# Custom_USB_N64.net
KiCad netlist of a schematic drawn in EAGLE
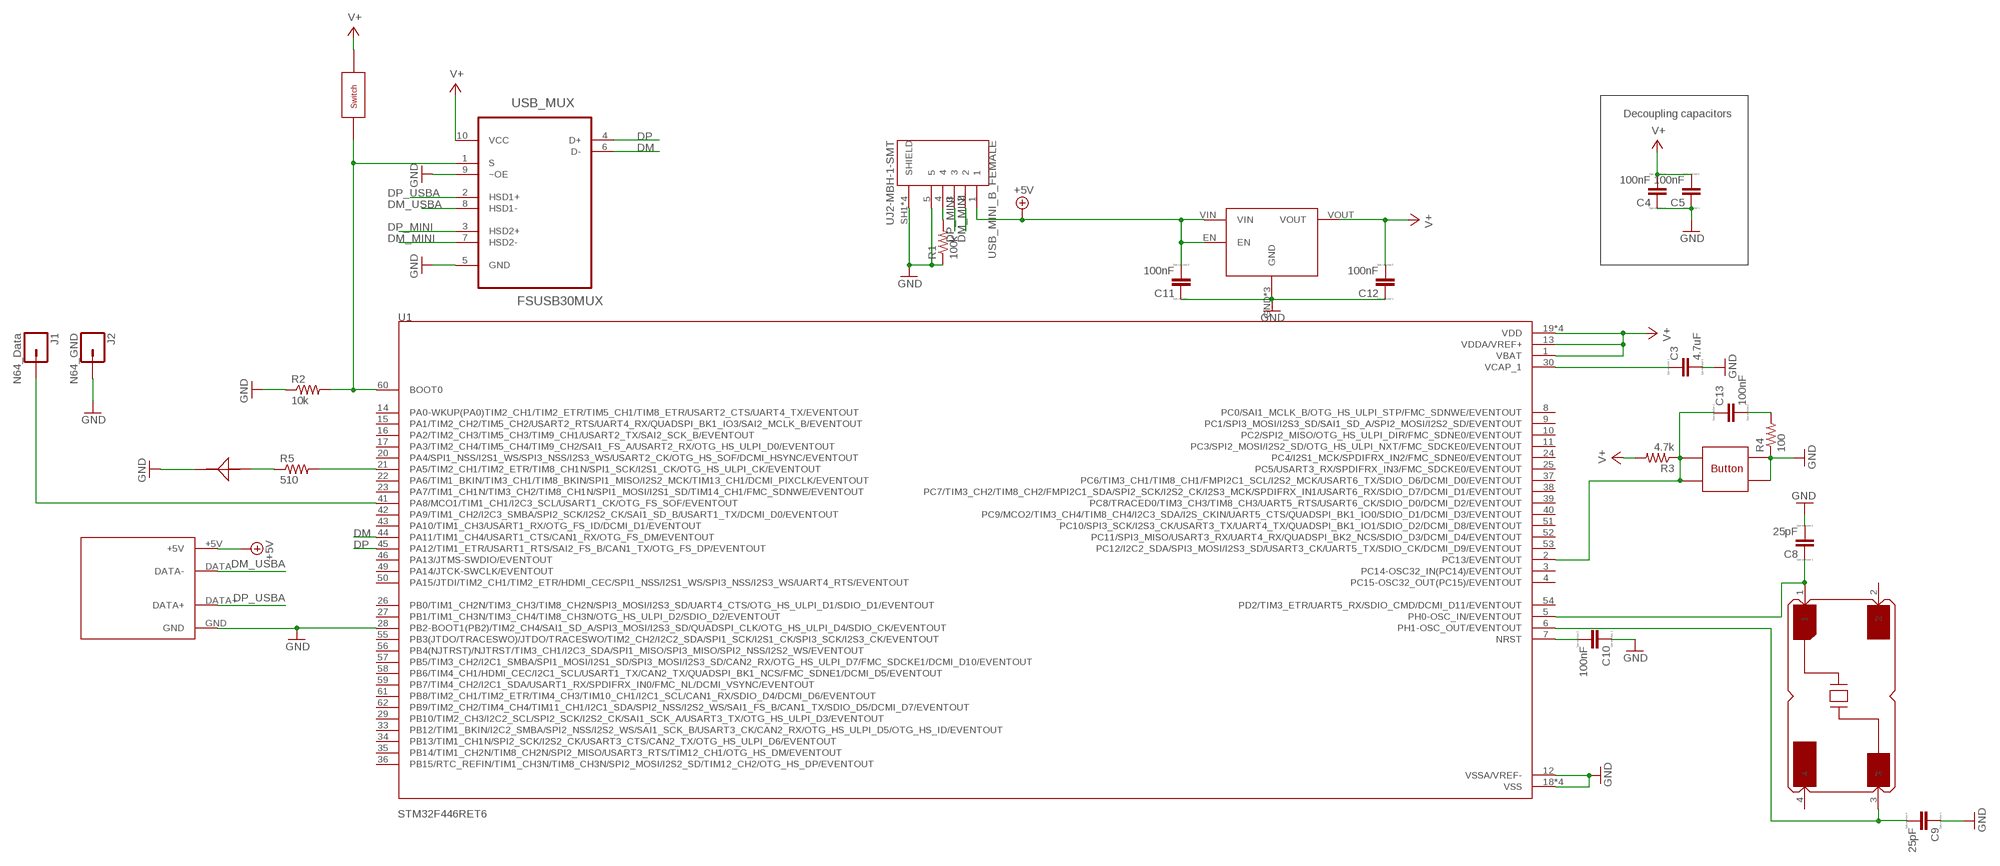
[diagram p0: schematic, sheet 1]

(export (version "E")
  (design (tool "Eeschema 10.0.6"))
  (components
    (comp (ref "C3")
      (value "4.7uF")
      (footprint "eagle-import:C0805")
      (libsource (lib "eagle-import") (part "C"))
    )
    (comp (ref "C4")
      (value "100nF")
      (footprint "eagle-import:C0805")
      (libsource (lib "eagle-import") (part "C"))
    )
    (comp (ref "C5")
      (value "100nF")
      (footprint "eagle-import:C0805")
      (libsource (lib "eagle-import") (part "C"))
    )
    (comp (ref "C8")
      (value "25pF")
      (footprint "eagle-import:C0805")
      (libsource (lib "eagle-import") (part "C"))
    )
    (comp (ref "C9")
      (value "25pF")
      (footprint "eagle-import:C0805")
      (libsource (lib "eagle-import") (part "C"))
    )
    (comp (ref "C10")
      (value "100nF")
      (footprint "eagle-import:C0805")
      (libsource (lib "eagle-import") (part "C"))
    )
    (comp (ref "C11")
      (value "100nF")
      (footprint "eagle-import:C0805")
      (libsource (lib "eagle-import") (part "C"))
    )
    (comp (ref "C12")
      (value "100nF")
      (footprint "eagle-import:C0805")
      (libsource (lib "eagle-import") (part "C"))
    )
    (comp (ref "C13")
      (value "100nF")
      (footprint "eagle-import:C0805")
      (libsource (lib "eagle-import") (part "C"))
    )
    (comp (ref "CHANGE_CONTROLS")
      (value "PUSHBUTTON")
      (footprint "eagle-import:PUSHBUTTON")
      (libsource (lib "eagle-import") (part "PUSHBUTTON"))
    )
    (comp (ref "J1")
      (value "N64_Data")
      (footprint "eagle-import:1X01")
      (libsource (lib "eagle-import") (part "M01PTH"))
    )
    (comp (ref "J2")
      (value "N64_GND")
      (footprint "eagle-import:1X01")
      (libsource (lib "eagle-import") (part "M01PTH"))
    )
    (comp (ref "R1")
      (value "100k")
      (footprint "eagle-import:R0805")
      (libsource (lib "eagle-import") (part "R-US_R0805"))
    )
    (comp (ref "R2")
      (value "10k")
      (footprint "eagle-import:R0805")
      (libsource (lib "eagle-import") (part "R-US_R0805"))
    )
    (comp (ref "R3")
      (value "4.7k")
      (footprint "eagle-import:R0805")
      (libsource (lib "eagle-import") (part "R-US_R0805"))
    )
    (comp (ref "R4")
      (value "100")
      (footprint "eagle-import:R0805")
      (libsource (lib "eagle-import") (part "R-US_R0805"))
    )
    (comp (ref "R5")
      (value "510")
      (footprint "eagle-import:R0805")
      (libsource (lib "eagle-import") (part "R-US_R0805"))
    )
    (comp (ref "SWITCH")
      (value "DM01")
      (footprint "eagle-import:DM01")
      (libsource (lib "eagle-import") (part "DM01"))
    )
    (comp (ref "U$6")
      (value "17-21SYGC/S530-E2/TR8")
      (footprint "eagle-import:17-21SYGC_S530-E2_TR8")
      (libsource (lib "eagle-import") (part "17-21SYGC/S530-E2/TR8"))
    )
    (comp (ref "U1")
      (value "STM32F446RET6")
      (footprint "eagle-import:QFP50P1200X1200X160-64N")
      (fields (field (name "MF") "STMicroelectronics"))
      (libsource (lib "eagle-import") (part "STM32F446RET6"))
    )
    (comp (ref "USB_A_FEMALE")
      (value "USB_A_F")
      (footprint "eagle-import:USB_A_F")
      (libsource (lib "eagle-import") (part "USB_A_F"))
    )
    (comp (ref "USB_MINI_B_FEMALE")
      (value "UJ2-MBH-1-SMT")
      (footprint "eagle-import:CUI_UJ2-MBH-1-SMT")
      (fields (field (name "MF") "CUI") (field (name "MP") "UJ2-MBH-1-SMT-TR"))
      (libsource (lib "eagle-import") (part "UJ2-MBH-1-SMT"))
    )
    (comp (ref "USB_MUX")
      (value "FSUSB30MUX")
      (footprint "eagle-import:SOP50P490X110-10N")
      (fields (field (name "MF") "ON Semiconductor"))
      (libsource (lib "eagle-import") (part "FSUSB30MUX"))
    )
    (comp (ref "V_REG")
      (value "S-1172B33-U5T1G")
      (footprint "eagle-import:S-1172B33-U5T1G")
      (libsource (lib "eagle-import") (part "S-1172B33-U5T1G"))
    )
    (comp (ref "XTAL_HSE")
      (value "ABMM-8.000MHZ-B2-T")
      (footprint "eagle-import:DFN-4")
      (fields (field (name "MF") "Abracon"))
      (libsource (lib "eagle-import") (part "ABMM-8.000MHZ-B2-T"))
    )
  )
  (nets
    (net (code "1") (name "+5V") (class "Default")
      (node (ref "C11") (pin "2") (pinfunction "2_2") (pintype "passive"))
      (node (ref "USB_A_FEMALE") (pin "+5V") (pinfunction "+5V_+5V") (pintype "bidirectional"))
      (node (ref "USB_MINI_B_FEMALE") (pin "1") (pinfunction "1_1") (pintype "passive"))
      (node (ref "V_REG") (pin "EN") (pinfunction "EN_EN") (pintype "bidirectional"))
      (node (ref "V_REG") (pin "VIN") (pinfunction "VIN_VIN") (pintype "bidirectional"))
    )
    (net (code "2") (name "/DM") (class "Default")
      (node (ref "U1") (pin "44") (pinfunction "PA11/TIM1_CH4/USART1_CTS/CAN1_RX/OTG_FS_DM/EVENTOUT_44") (pintype "bidirectional"))
      (node (ref "USB_MUX") (pin "6") (pinfunction "D-_6") (pintype "bidirectional"))
    )
    (net (code "3") (name "/DM_MINI") (class "Default")
      (node (ref "USB_MINI_B_FEMALE") (pin "2") (pinfunction "2_2") (pintype "passive"))
      (node (ref "USB_MUX") (pin "7") (pinfunction "HSD2-_7") (pintype "bidirectional"))
    )
    (net (code "4") (name "/DM_USBA") (class "Default")
      (node (ref "USB_A_FEMALE") (pin "DATA-") (pinfunction "DATA-_DATA-") (pintype "bidirectional"))
      (node (ref "USB_MUX") (pin "8") (pinfunction "HSD1-_8") (pintype "bidirectional"))
    )
    (net (code "5") (name "/DP") (class "Default")
      (node (ref "U1") (pin "45") (pinfunction "PA12/TIM1_ETR/USART1_RTS/SAI2_FS_B/CAN1_TX/OTG_FS_DP/EVENTOUT_45") (pintype "bidirectional"))
      (node (ref "USB_MUX") (pin "4") (pinfunction "D+_4") (pintype "bidirectional"))
    )
    (net (code "6") (name "/DP_MINI") (class "Default")
      (node (ref "USB_MINI_B_FEMALE") (pin "3") (pinfunction "3_3") (pintype "passive"))
      (node (ref "USB_MUX") (pin "3") (pinfunction "HSD2+_3") (pintype "bidirectional"))
    )
    (net (code "7") (name "/DP_USBA") (class "Default")
      (node (ref "USB_A_FEMALE") (pin "DATA+") (pinfunction "DATA+_DATA+") (pintype "bidirectional"))
      (node (ref "USB_MUX") (pin "2") (pinfunction "HSD1+_2") (pintype "bidirectional"))
    )
    (net (code "8") (name "GND") (class "Default")
      (node (ref "C10") (pin "1") (pinfunction "1_1") (pintype "passive"))
      (node (ref "C11") (pin "1") (pinfunction "1_1") (pintype "passive"))
      (node (ref "C12") (pin "1") (pinfunction "1_1") (pintype "passive"))
      (node (ref "C3") (pin "2") (pinfunction "2_2") (pintype "passive"))
      (node (ref "C4") (pin "1") (pinfunction "1_1") (pintype "passive"))
      (node (ref "C5") (pin "1") (pinfunction "1_1") (pintype "passive"))
      (node (ref "C8") (pin "2") (pinfunction "2_2") (pintype "passive"))
      (node (ref "C9") (pin "1") (pinfunction "1_1") (pintype "passive"))
      (node (ref "CHANGE_CONTROLS") (pin "P$3") (pinfunction "P$3_P$3") (pintype "bidirectional"))
      (node (ref "CHANGE_CONTROLS") (pin "P$4") (pinfunction "P$4_P$4") (pintype "bidirectional"))
      (node (ref "J2") (pin "1") (pinfunction "1_1") (pintype "passive"))
      (node (ref "R1") (pin "1") (pinfunction "1_1") (pintype "passive"))
      (node (ref "R2") (pin "1") (pinfunction "1_1") (pintype "passive"))
      (node (ref "R4") (pin "1") (pinfunction "1_1") (pintype "passive"))
      (node (ref "U$6") (pin "NEG") (pinfunction "NEG_NEG") (pintype "bidirectional"))
      (node (ref "U1") (pin "12") (pinfunction "VSSA/VREF-_12") (pintype "power_in"))
      (node (ref "U1") (pin "18") (pinfunction "VSS_18") (pintype "power_in"))
      (node (ref "U1") (pin "28") (pinfunction "PB2-BOOT1(PB2)/TIM2_CH4/SAI1_SD_A/SPI3_MOSI/I2S3_SD/QUADSPI_CLK/OTG_HS_ULPI_D4/SDIO_CK/EVENTOUT_28") (pintype "bidirectional"))
      (node (ref "U1") (pin "31") (pinfunction "VSS_31") (pintype "power_in"))
      (node (ref "U1") (pin "47") (pinfunction "VSS_47") (pintype "power_in"))
      (node (ref "U1") (pin "63") (pinfunction "VSS_63") (pintype "power_in"))
      (node (ref "USB_A_FEMALE") (pin "GND") (pinfunction "GND_GND") (pintype "bidirectional"))
      (node (ref "USB_MINI_B_FEMALE") (pin "5") (pinfunction "5_5") (pintype "passive"))
      (node (ref "USB_MINI_B_FEMALE") (pin "SH1") (pinfunction "SHIELD_SH1") (pintype "passive"))
      (node (ref "USB_MINI_B_FEMALE") (pin "SH2") (pinfunction "SHIELD_SH2") (pintype "passive"))
      (node (ref "USB_MINI_B_FEMALE") (pin "SH3") (pinfunction "SHIELD_SH3") (pintype "passive"))
      (node (ref "USB_MINI_B_FEMALE") (pin "SH4") (pinfunction "SHIELD_SH4") (pintype "passive"))
      (node (ref "USB_MUX") (pin "5") (pinfunction "GND_5") (pintype "passive"))
      (node (ref "USB_MUX") (pin "9") (pinfunction "~{OE}_9") (pintype "input"))
      (node (ref "V_REG") (pin "GND") (pinfunction "GND_GND") (pintype "bidirectional"))
      (node (ref "V_REG") (pin "GND2") (pinfunction "GND_GND2") (pintype "bidirectional"))
      (node (ref "V_REG") (pin "GND3") (pinfunction "GND_GND3") (pintype "bidirectional"))
    )
    (net (code "9") (name "Net-(C13-Pad2)") (class "Default")
      (node (ref "C13") (pin "2") (pinfunction "2_2") (pintype "passive"))
      (node (ref "R4") (pin "2") (pinfunction "2_2") (pintype "passive"))
    )
    (net (code "10") (name "Net-(R1-Pad2)") (class "Default")
      (node (ref "R1") (pin "2") (pinfunction "2_2") (pintype "passive"))
      (node (ref "USB_MINI_B_FEMALE") (pin "4") (pinfunction "4_4") (pintype "passive"))
    )
    (net (code "11") (name "Net-(R5-Pad1)") (class "Default")
      (node (ref "R5") (pin "1") (pinfunction "1_1") (pintype "passive"))
      (node (ref "U$6") (pin "POS") (pinfunction "POS_POS") (pintype "bidirectional"))
    )
    (net (code "12") (name "Net-(U1-BOOT0)") (class "Default")
      (node (ref "R2") (pin "2") (pinfunction "2_2") (pintype "passive"))
      (node (ref "SWITCH") (pin "P$2") (pinfunction "P$2_P$2") (pintype "bidirectional"))
      (node (ref "U1") (pin "60") (pinfunction "BOOT0_60") (pintype "input"))
      (node (ref "USB_MUX") (pin "1") (pinfunction "S_1") (pintype "input"))
    )
    (net (code "13") (name "Net-(U1-NRST)") (class "Default")
      (node (ref "C10") (pin "2") (pinfunction "2_2") (pintype "passive"))
      (node (ref "U1") (pin "7") (pinfunction "NRST_7") (pintype "bidirectional"))
    )
    (net (code "14") (name "Net-(U1-PA5{slash}TIM2_CH1{slash}TIM2_ETR{slash}TIM8_CH1N{slash}SPI1_SCK{slash}I2S1_CK{slash}OTG_HS_ULPI_CK{slash}EVENTOUT)") (class "Default")
      (node (ref "R5") (pin "2") (pinfunction "2_2") (pintype "passive"))
      (node (ref "U1") (pin "21") (pinfunction "PA5/TIM2_CH1/TIM2_ETR/TIM8_CH1N/SPI1_SCK/I2S1_CK/OTG_HS_ULPI_CK/EVENTOUT_21") (pintype "bidirectional"))
    )
    (net (code "15") (name "Net-(U1-PA8{slash}MCO1{slash}TIM1_CH1{slash}I2C3_SCL{slash}USART1_CK{slash}OTG_FS_SOF{slash}EVENTOUT)") (class "Default")
      (node (ref "J1") (pin "1") (pinfunction "1_1") (pintype "passive"))
      (node (ref "U1") (pin "41") (pinfunction "PA8/MCO1/TIM1_CH1/I2C3_SCL/USART1_CK/OTG_FS_SOF/EVENTOUT_41") (pintype "bidirectional"))
    )
    (net (code "16") (name "Net-(U1-PC13{slash}EVENTOUT)") (class "Default")
      (node (ref "C13") (pin "1") (pinfunction "1_1") (pintype "passive"))
      (node (ref "CHANGE_CONTROLS") (pin "P$1") (pinfunction "P$1_P$1") (pintype "bidirectional"))
      (node (ref "CHANGE_CONTROLS") (pin "P$2") (pinfunction "P$2_P$2") (pintype "bidirectional"))
      (node (ref "R3") (pin "1") (pinfunction "1_1") (pintype "passive"))
      (node (ref "U1") (pin "2") (pinfunction "PC13/EVENTOUT_2") (pintype "bidirectional"))
    )
    (net (code "17") (name "Net-(U1-PH0-OSC_IN{slash}EVENTOUT)") (class "Default")
      (node (ref "C8") (pin "1") (pinfunction "1_1") (pintype "passive"))
      (node (ref "U1") (pin "5") (pinfunction "PH0-OSC_IN/EVENTOUT_5") (pintype "bidirectional"))
      (node (ref "XTAL_HSE") (pin "1") (pinfunction "1_1") (pintype "bidirectional"))
    )
    (net (code "18") (name "Net-(U1-PH1-OSC_OUT{slash}EVENTOUT)") (class "Default")
      (node (ref "C9") (pin "2") (pinfunction "2_2") (pintype "passive"))
      (node (ref "U1") (pin "6") (pinfunction "PH1-OSC_OUT/EVENTOUT_6") (pintype "bidirectional"))
      (node (ref "XTAL_HSE") (pin "3") (pinfunction "3_3") (pintype "bidirectional"))
    )
    (net (code "19") (name "Net-(U1-VCAP_1)") (class "Default")
      (node (ref "C3") (pin "1") (pinfunction "1_1") (pintype "passive"))
      (node (ref "U1") (pin "30") (pinfunction "VCAP_1_30") (pintype "power_in"))
    )
    (net (code "20") (name "V+") (class "Default")
      (node (ref "C12") (pin "2") (pinfunction "2_2") (pintype "passive"))
      (node (ref "C4") (pin "2") (pinfunction "2_2") (pintype "passive"))
      (node (ref "C5") (pin "2") (pinfunction "2_2") (pintype "passive"))
      (node (ref "R3") (pin "2") (pinfunction "2_2") (pintype "passive"))
      (node (ref "SWITCH") (pin "P$1") (pinfunction "P$1_P$1") (pintype "bidirectional"))
      (node (ref "U1") (pin "1") (pinfunction "VBAT_1") (pintype "power_in"))
      (node (ref "U1") (pin "13") (pinfunction "VDDA/VREF+_13") (pintype "power_in"))
      (node (ref "U1") (pin "19") (pinfunction "VDD_19") (pintype "power_in"))
      (node (ref "U1") (pin "32") (pinfunction "VDD_32") (pintype "power_in"))
      (node (ref "U1") (pin "48") (pinfunction "VDD_48") (pintype "power_in"))
      (node (ref "U1") (pin "64") (pinfunction "VDD_64") (pintype "power_in"))
      (node (ref "USB_MUX") (pin "10") (pinfunction "VCC_10") (pintype "power_in"))
      (node (ref "V_REG") (pin "VOUT") (pinfunction "VOUT_VOUT") (pintype "bidirectional"))
    )
    (net (code "21") (name "unconnected-(U1-PA0-WKUP(PA0)TIM2_CH1{slash}TIM2_ETR{slash}TIM5_CH1{slash}TIM8_ETR{slash}USART2_CTS{slash}UART4_TX{slash}EVENTOUT-Pad14)") (class "Default")
      (node (ref "U1") (pin "14") (pinfunction "PA0-WKUP(PA0)TIM2_CH1/TIM2_ETR/TIM5_CH1/TIM8_ETR/USART2_CTS/UART4_TX/EVENTOUT_14") (pintype "bidirectional"))
    )
    (net (code "22") (name "unconnected-(U1-PA1{slash}TIM2_CH2{slash}TIM5_CH2{slash}USART2_RTS{slash}UART4_RX{slash}QUADSPI_BK1_IO3{slash}SAI2_MCLK_B{slash}EVENTOUT-Pad15)") (class "Default")
      (node (ref "U1") (pin "15") (pinfunction "PA1/TIM2_CH2/TIM5_CH2/USART2_RTS/UART4_RX/QUADSPI_BK1_IO3/SAI2_MCLK_B/EVENTOUT_15") (pintype "bidirectional"))
    )
    (net (code "23") (name "unconnected-(U1-PA2{slash}TIM2_CH3{slash}TIM5_CH3{slash}TIM9_CH1{slash}USART2_TX{slash}SAI2_SCK_B{slash}EVENTOUT-Pad16)") (class "Default")
      (node (ref "U1") (pin "16") (pinfunction "PA2/TIM2_CH3/TIM5_CH3/TIM9_CH1/USART2_TX/SAI2_SCK_B/EVENTOUT_16") (pintype "bidirectional"))
    )
    (net (code "24") (name "unconnected-(U1-PA3{slash}TIM2_CH4{slash}TIM5_CH4{slash}TIM9_CH2{slash}SAI1_FS_A{slash}USART2_RX{slash}OTG_HS_ULPI_D0{slash}EVENTOUT-Pad17)") (class "Default")
      (node (ref "U1") (pin "17") (pinfunction "PA3/TIM2_CH4/TIM5_CH4/TIM9_CH2/SAI1_FS_A/USART2_RX/OTG_HS_ULPI_D0/EVENTOUT_17") (pintype "bidirectional"))
    )
    (net (code "25") (name "unconnected-(U1-PA4{slash}SPI1_NSS{slash}I2S1_WS{slash}SPI3_NSS{slash}I2S3_WS{slash}USART2_CK{slash}OTG_HS_SOF{slash}DCMI_HSYNC{slash}EVENTOUT-Pad20)") (class "Default")
      (node (ref "U1") (pin "20") (pinfunction "PA4/SPI1_NSS/I2S1_WS/SPI3_NSS/I2S3_WS/USART2_CK/OTG_HS_SOF/DCMI_HSYNC/EVENTOUT_20") (pintype "bidirectional"))
    )
    (net (code "26") (name "unconnected-(U1-PA6{slash}TIM1_BKIN{slash}TIM3_CH1{slash}TIM8_BKIN{slash}SPI1_MISO{slash}I2S2_MCK{slash}TIM13_CH1{slash}DCMI_PIXCLK{slash}EVENTOUT-Pad22)") (class "Default")
      (node (ref "U1") (pin "22") (pinfunction "PA6/TIM1_BKIN/TIM3_CH1/TIM8_BKIN/SPI1_MISO/I2S2_MCK/TIM13_CH1/DCMI_PIXCLK/EVENTOUT_22") (pintype "bidirectional"))
    )
    (net (code "27") (name "unconnected-(U1-PA7{slash}TIM1_CH1N{slash}TIM3_CH2{slash}TIM8_CH1N{slash}SPI1_MOSI{slash}I2S1_SD{slash}TIM14_CH1{slash}FMC_SDNWE{slash}EVENTOUT-Pad23)") (class "Default")
      (node (ref "U1") (pin "23") (pinfunction "PA7/TIM1_CH1N/TIM3_CH2/TIM8_CH1N/SPI1_MOSI/I2S1_SD/TIM14_CH1/FMC_SDNWE/EVENTOUT_23") (pintype "bidirectional"))
    )
    (net (code "28") (name "unconnected-(U1-PA9{slash}TIM1_CH2{slash}I2C3_SMBA{slash}SPI2_SCK{slash}I2S2_CK{slash}SAI1_SD_B{slash}USART1_TX{slash}DCMI_D0{slash}EVENTOUT-Pad42)") (class "Default")
      (node (ref "U1") (pin "42") (pinfunction "PA9/TIM1_CH2/I2C3_SMBA/SPI2_SCK/I2S2_CK/SAI1_SD_B/USART1_TX/DCMI_D0/EVENTOUT_42") (pintype "bidirectional"))
    )
    (net (code "29") (name "unconnected-(U1-PA10{slash}TIM1_CH3{slash}USART1_RX{slash}OTG_FS_ID{slash}DCMI_D1{slash}EVENTOUT-Pad43)") (class "Default")
      (node (ref "U1") (pin "43") (pinfunction "PA10/TIM1_CH3/USART1_RX/OTG_FS_ID/DCMI_D1/EVENTOUT_43") (pintype "bidirectional"))
    )
    (net (code "30") (name "unconnected-(U1-PA13{slash}JTMS-SWDIO{slash}EVENTOUT-Pad46)") (class "Default")
      (node (ref "U1") (pin "46") (pinfunction "PA13/JTMS-SWDIO/EVENTOUT_46") (pintype "bidirectional"))
    )
    (net (code "31") (name "unconnected-(U1-PA14{slash}JTCK-SWCLK{slash}EVENTOUT-Pad49)") (class "Default")
      (node (ref "U1") (pin "49") (pinfunction "PA14/JTCK-SWCLK/EVENTOUT_49") (pintype "bidirectional"))
    )
    (net (code "32") (name "unconnected-(U1-PA15{slash}JTDI{slash}TIM2_CH1{slash}TIM2_ETR{slash}HDMI_CEC{slash}SPI1_NSS{slash}I2S1_WS{slash}SPI3_NSS{slash}I2S3_WS{slash}UART4_RTS{slash}EVENTOUT-Pad50)") (class "Default")
      (node (ref "U1") (pin "50") (pinfunction "PA15/JTDI/TIM2_CH1/TIM2_ETR/HDMI_CEC/SPI1_NSS/I2S1_WS/SPI3_NSS/I2S3_WS/UART4_RTS/EVENTOUT_50") (pintype "bidirectional"))
    )
    (net (code "33") (name "unconnected-(U1-PB0{slash}TIM1_CH2N{slash}TIM3_CH3{slash}TIM8_CH2N{slash}SPI3_MOSI{slash}I2S3_SD{slash}UART4_CTS{slash}OTG_HS_ULPI_D1{slash}SDIO_D1{slash}EVENTOUT-Pad26)") (class "Default")
      (node (ref "U1") (pin "26") (pinfunction "PB0/TIM1_CH2N/TIM3_CH3/TIM8_CH2N/SPI3_MOSI/I2S3_SD/UART4_CTS/OTG_HS_ULPI_D1/SDIO_D1/EVENTOUT_26") (pintype "bidirectional"))
    )
    (net (code "34") (name "unconnected-(U1-PB1{slash}TIM1_CH3N{slash}TIM3_CH4{slash}TIM8_CH3N{slash}OTG_HS_ULPI_D2{slash}SDIO_D2{slash}EVENTOUT-Pad27)") (class "Default")
      (node (ref "U1") (pin "27") (pinfunction "PB1/TIM1_CH3N/TIM3_CH4/TIM8_CH3N/OTG_HS_ULPI_D2/SDIO_D2/EVENTOUT_27") (pintype "bidirectional"))
    )
    (net (code "35") (name "unconnected-(U1-PB3(JTDO{slash}TRACESWO){slash}JTDO{slash}TRACESWO{slash}TIM2_CH2{slash}I2C2_SDA{slash}SPI1_SCK{slash}I2S1_CK{slash}SPI3_SCK{slash}I2S3_CK{slash}EVENTOUT-Pad55)") (class "Default")
      (node (ref "U1") (pin "55") (pinfunction "PB3(JTDO/TRACESWO)/JTDO/TRACESWO/TIM2_CH2/I2C2_SDA/SPI1_SCK/I2S1_CK/SPI3_SCK/I2S3_CK/EVENTOUT_55") (pintype "bidirectional"))
    )
    (net (code "36") (name "unconnected-(U1-PB4(NJTRST){slash}NJTRST{slash}TIM3_CH1{slash}I2C3_SDA{slash}SPI1_MISO{slash}SPI3_MISO{slash}SPI2_NSS{slash}I2S2_WS{slash}EVENTOUT-Pad56)") (class "Default")
      (node (ref "U1") (pin "56") (pinfunction "PB4(NJTRST)/NJTRST/TIM3_CH1/I2C3_SDA/SPI1_MISO/SPI3_MISO/SPI2_NSS/I2S2_WS/EVENTOUT_56") (pintype "bidirectional"))
    )
    (net (code "37") (name "unconnected-(U1-PB5{slash}TIM3_CH2{slash}I2C1_SMBA{slash}SPI1_MOSI{slash}I2S1_SD{slash}SPI3_MOSI{slash}I2S3_SD{slash}CAN2_RX{slash}OTG_HS_ULPI_D7{slash}FMC_SDCKE1{slash}DCMI_D10{slash}EVENTOUT-Pad57)") (class "Default")
      (node (ref "U1") (pin "57") (pinfunction "PB5/TIM3_CH2/I2C1_SMBA/SPI1_MOSI/I2S1_SD/SPI3_MOSI/I2S3_SD/CAN2_RX/OTG_HS_ULPI_D7/FMC_SDCKE1/DCMI_D10/EVENTOUT_57") (pintype "bidirectional"))
    )
    (net (code "38") (name "unconnected-(U1-PB6{slash}TIM4_CH1{slash}HDMI_CEC{slash}I2C1_SCL{slash}USART1_TX{slash}CAN2_TX{slash}QUADSPI_BK1_NCS{slash}FMC_SDNE1{slash}DCMI_D5{slash}EVENTOUT-Pad58)") (class "Default")
      (node (ref "U1") (pin "58") (pinfunction "PB6/TIM4_CH1/HDMI_CEC/I2C1_SCL/USART1_TX/CAN2_TX/QUADSPI_BK1_NCS/FMC_SDNE1/DCMI_D5/EVENTOUT_58") (pintype "bidirectional"))
    )
    (net (code "39") (name "unconnected-(U1-PB7{slash}TIM4_CH2{slash}I2C1_SDA{slash}USART1_RX{slash}SPDIFRX_IN0{slash}FMC_NL{slash}DCMI_VSYNC{slash}EVENTOUT-Pad59)") (class "Default")
      (node (ref "U1") (pin "59") (pinfunction "PB7/TIM4_CH2/I2C1_SDA/USART1_RX/SPDIFRX_IN0/FMC_NL/DCMI_VSYNC/EVENTOUT_59") (pintype "bidirectional"))
    )
    (net (code "40") (name "unconnected-(U1-PB8{slash}TIM2_CH1{slash}TIM2_ETR{slash}TIM4_CH3{slash}TIM10_CH1{slash}I2C1_SCL{slash}CAN1_RX{slash}SDIO_D4{slash}DCMI_D6{slash}EVENTOUT-Pad61)") (class "Default")
      (node (ref "U1") (pin "61") (pinfunction "PB8/TIM2_CH1/TIM2_ETR/TIM4_CH3/TIM10_CH1/I2C1_SCL/CAN1_RX/SDIO_D4/DCMI_D6/EVENTOUT_61") (pintype "bidirectional"))
    )
    (net (code "41") (name "unconnected-(U1-PB9{slash}TIM2_CH2{slash}TIM4_CH4{slash}TIM11_CH1{slash}I2C1_SDA{slash}SPI2_NSS{slash}I2S2_WS{slash}SAI1_FS_B{slash}CAN1_TX{slash}SDIO_D5{slash}DCMI_D7{slash}EVENTOUT-Pad62)") (class "Default")
      (node (ref "U1") (pin "62") (pinfunction "PB9/TIM2_CH2/TIM4_CH4/TIM11_CH1/I2C1_SDA/SPI2_NSS/I2S2_WS/SAI1_FS_B/CAN1_TX/SDIO_D5/DCMI_D7/EVENTOUT_62") (pintype "bidirectional"))
    )
    (net (code "42") (name "unconnected-(U1-PB10{slash}TIM2_CH3{slash}I2C2_SCL{slash}SPI2_SCK{slash}I2S2_CK{slash}SAI1_SCK_A{slash}USART3_TX{slash}OTG_HS_ULPI_D3{slash}EVENTOUT-Pad29)") (class "Default")
      (node (ref "U1") (pin "29") (pinfunction "PB10/TIM2_CH3/I2C2_SCL/SPI2_SCK/I2S2_CK/SAI1_SCK_A/USART3_TX/OTG_HS_ULPI_D3/EVENTOUT_29") (pintype "bidirectional"))
    )
    (net (code "43") (name "unconnected-(U1-PB12{slash}TIM1_BKIN{slash}I2C2_SMBA{slash}SPI2_NSS{slash}I2S2_WS{slash}SAI1_SCK_B{slash}USART3_CK{slash}CAN2_RX{slash}OTG_HS_ULPI_D5{slash}OTG_HS_ID{slash}EVENTOUT-Pad33)") (class "Default")
      (node (ref "U1") (pin "33") (pinfunction "PB12/TIM1_BKIN/I2C2_SMBA/SPI2_NSS/I2S2_WS/SAI1_SCK_B/USART3_CK/CAN2_RX/OTG_HS_ULPI_D5/OTG_HS_ID/EVENTOUT_33") (pintype "bidirectional"))
    )
    (net (code "44") (name "unconnected-(U1-PB13{slash}TIM1_CH1N{slash}SPI2_SCK{slash}I2S2_CK{slash}USART3_CTS{slash}CAN2_TX{slash}OTG_HS_ULPI_D6{slash}EVENTOUT-Pad34)") (class "Default")
      (node (ref "U1") (pin "34") (pinfunction "PB13/TIM1_CH1N/SPI2_SCK/I2S2_CK/USART3_CTS/CAN2_TX/OTG_HS_ULPI_D6/EVENTOUT_34") (pintype "bidirectional"))
    )
    (net (code "45") (name "unconnected-(U1-PB14{slash}TIM1_CH2N{slash}TIM8_CH2N{slash}SPI2_MISO{slash}USART3_RTS{slash}TIM12_CH1{slash}OTG_HS_DM{slash}EVENTOUT-Pad35)") (class "Default")
      (node (ref "U1") (pin "35") (pinfunction "PB14/TIM1_CH2N/TIM8_CH2N/SPI2_MISO/USART3_RTS/TIM12_CH1/OTG_HS_DM/EVENTOUT_35") (pintype "bidirectional"))
    )
    (net (code "46") (name "unconnected-(U1-PB15{slash}RTC_REFIN{slash}TIM1_CH3N{slash}TIM8_CH3N{slash}SPI2_MOSI{slash}I2S2_SD{slash}TIM12_CH2{slash}OTG_HS_DP{slash}EVENTOUT-Pad36)") (class "Default")
      (node (ref "U1") (pin "36") (pinfunction "PB15/RTC_REFIN/TIM1_CH3N/TIM8_CH3N/SPI2_MOSI/I2S2_SD/TIM12_CH2/OTG_HS_DP/EVENTOUT_36") (pintype "bidirectional"))
    )
    (net (code "47") (name "unconnected-(U1-PC0{slash}SAI1_MCLK_B{slash}OTG_HS_ULPI_STP{slash}FMC_SDNWE{slash}EVENTOUT-Pad8)") (class "Default")
      (node (ref "U1") (pin "8") (pinfunction "PC0/SAI1_MCLK_B/OTG_HS_ULPI_STP/FMC_SDNWE/EVENTOUT_8") (pintype "bidirectional"))
    )
    (net (code "48") (name "unconnected-(U1-PC1{slash}SPI3_MOSI{slash}I2S3_SD{slash}SAI1_SD_A{slash}SPI2_MOSI{slash}I2S2_SD{slash}EVENTOUT-Pad9)") (class "Default")
      (node (ref "U1") (pin "9") (pinfunction "PC1/SPI3_MOSI/I2S3_SD/SAI1_SD_A/SPI2_MOSI/I2S2_SD/EVENTOUT_9") (pintype "bidirectional"))
    )
    (net (code "49") (name "unconnected-(U1-PC2{slash}SPI2_MISO{slash}OTG_HS_ULPI_DIR{slash}FMC_SDNE0{slash}EVENTOUT-Pad10)") (class "Default")
      (node (ref "U1") (pin "10") (pinfunction "PC2/SPI2_MISO/OTG_HS_ULPI_DIR/FMC_SDNE0/EVENTOUT_10") (pintype "bidirectional"))
    )
    (net (code "50") (name "unconnected-(U1-PC3{slash}SPI2_MOSI{slash}I2S2_SD{slash}OTG_HS_ULPI_NXT{slash}FMC_SDCKE0{slash}EVENTOUT-Pad11)") (class "Default")
      (node (ref "U1") (pin "11") (pinfunction "PC3/SPI2_MOSI/I2S2_SD/OTG_HS_ULPI_NXT/FMC_SDCKE0/EVENTOUT_11") (pintype "bidirectional"))
    )
    (net (code "51") (name "unconnected-(U1-PC4{slash}I2S1_MCK{slash}SPDIFRX_IN2{slash}FMC_SDNE0{slash}EVENTOUT-Pad24)") (class "Default")
      (node (ref "U1") (pin "24") (pinfunction "PC4/I2S1_MCK/SPDIFRX_IN2/FMC_SDNE0/EVENTOUT_24") (pintype "bidirectional"))
    )
    (net (code "52") (name "unconnected-(U1-PC5{slash}USART3_RX{slash}SPDIFRX_IN3{slash}FMC_SDCKE0{slash}EVENTOUT-Pad25)") (class "Default")
      (node (ref "U1") (pin "25") (pinfunction "PC5/USART3_RX/SPDIFRX_IN3/FMC_SDCKE0/EVENTOUT_25") (pintype "bidirectional"))
    )
    (net (code "53") (name "unconnected-(U1-PC6{slash}TIM3_CH1{slash}TIM8_CH1{slash}FMPI2C1_SCL{slash}I2S2_MCK{slash}USART6_TX{slash}SDIO_D6{slash}DCMI_D0{slash}EVENTOUT-Pad37)") (class "Default")
      (node (ref "U1") (pin "37") (pinfunction "PC6/TIM3_CH1/TIM8_CH1/FMPI2C1_SCL/I2S2_MCK/USART6_TX/SDIO_D6/DCMI_D0/EVENTOUT_37") (pintype "bidirectional"))
    )
    (net (code "54") (name "unconnected-(U1-PC7{slash}TIM3_CH2{slash}TIM8_CH2{slash}FMPI2C1_SDA{slash}SPI2_SCK{slash}I2S2_CK{slash}I2S3_MCK{slash}SPDIFRX_IN1{slash}USART6_RX{slash}SDIO_D7{slash}DCMI_D1{slash}EVENTOUT-Pad38)") (class "Default")
      (node (ref "U1") (pin "38") (pinfunction "PC7/TIM3_CH2/TIM8_CH2/FMPI2C1_SDA/SPI2_SCK/I2S2_CK/I2S3_MCK/SPDIFRX_IN1/USART6_RX/SDIO_D7/DCMI_D1/EVENTOUT_38") (pintype "bidirectional"))
    )
    (net (code "55") (name "unconnected-(U1-PC8{slash}TRACED0{slash}TIM3_CH3{slash}TIM8_CH3{slash}UART5_RTS{slash}USART6_CK{slash}SDIO_D0{slash}DCMI_D2{slash}EVENTOUT-Pad39)") (class "Default")
      (node (ref "U1") (pin "39") (pinfunction "PC8/TRACED0/TIM3_CH3/TIM8_CH3/UART5_RTS/USART6_CK/SDIO_D0/DCMI_D2/EVENTOUT_39") (pintype "bidirectional"))
    )
    (net (code "56") (name "unconnected-(U1-PC9{slash}MCO2{slash}TIM3_CH4{slash}TIM8_CH4{slash}I2C3_SDA{slash}I2S_CKIN{slash}UART5_CTS{slash}QUADSPI_BK1_IO0{slash}SDIO_D1{slash}DCMI_D3{slash}EVENTOUT-Pad40)") (class "Default")
      (node (ref "U1") (pin "40") (pinfunction "PC9/MCO2/TIM3_CH4/TIM8_CH4/I2C3_SDA/I2S_CKIN/UART5_CTS/QUADSPI_BK1_IO0/SDIO_D1/DCMI_D3/EVENTOUT_40") (pintype "bidirectional"))
    )
    (net (code "57") (name "unconnected-(U1-PC10{slash}SPI3_SCK{slash}I2S3_CK{slash}USART3_TX{slash}UART4_TX{slash}QUADSPI_BK1_IO1{slash}SDIO_D2{slash}DCMI_D8{slash}EVENTOUT-Pad51)") (class "Default")
      (node (ref "U1") (pin "51") (pinfunction "PC10/SPI3_SCK/I2S3_CK/USART3_TX/UART4_TX/QUADSPI_BK1_IO1/SDIO_D2/DCMI_D8/EVENTOUT_51") (pintype "bidirectional"))
    )
    (net (code "58") (name "unconnected-(U1-PC11{slash}SPI3_MISO{slash}USART3_RX{slash}UART4_RX{slash}QUADSPI_BK2_NCS{slash}SDIO_D3{slash}DCMI_D4{slash}EVENTOUT-Pad52)") (class "Default")
      (node (ref "U1") (pin "52") (pinfunction "PC11/SPI3_MISO/USART3_RX/UART4_RX/QUADSPI_BK2_NCS/SDIO_D3/DCMI_D4/EVENTOUT_52") (pintype "bidirectional"))
    )
    (net (code "59") (name "unconnected-(U1-PC12{slash}I2C2_SDA{slash}SPI3_MOSI{slash}I2S3_SD{slash}USART3_CK{slash}UART5_TX{slash}SDIO_CK{slash}DCMI_D9{slash}EVENTOUT-Pad53)") (class "Default")
      (node (ref "U1") (pin "53") (pinfunction "PC12/I2C2_SDA/SPI3_MOSI/I2S3_SD/USART3_CK/UART5_TX/SDIO_CK/DCMI_D9/EVENTOUT_53") (pintype "bidirectional"))
    )
    (net (code "60") (name "unconnected-(U1-PC14-OSC32_IN(PC14){slash}EVENTOUT-Pad3)") (class "Default")
      (node (ref "U1") (pin "3") (pinfunction "PC14-OSC32_IN(PC14)/EVENTOUT_3") (pintype "bidirectional"))
    )
    (net (code "61") (name "unconnected-(U1-PC15-OSC32_OUT(PC15){slash}EVENTOUT-Pad4)") (class "Default")
      (node (ref "U1") (pin "4") (pinfunction "PC15-OSC32_OUT(PC15)/EVENTOUT_4") (pintype "bidirectional"))
    )
    (net (code "62") (name "unconnected-(U1-PD2{slash}TIM3_ETR{slash}UART5_RX{slash}SDIO_CMD{slash}DCMI_D11{slash}EVENTOUT-Pad54)") (class "Default")
      (node (ref "U1") (pin "54") (pinfunction "PD2/TIM3_ETR/UART5_RX/SDIO_CMD/DCMI_D11/EVENTOUT_54") (pintype "bidirectional"))
    )
    (net (code "63") (name "unconnected-(XTAL_HSE-Pad2)") (class "Default")
      (node (ref "XTAL_HSE") (pin "2") (pinfunction "2_2") (pintype "bidirectional"))
    )
    (net (code "64") (name "unconnected-(XTAL_HSE-Pad4)") (class "Default")
      (node (ref "XTAL_HSE") (pin "4") (pinfunction "4_4") (pintype "bidirectional"))
    )
  )
)
